# ADC.net
KiCad netlist of a schematic drawn in Altium Designer
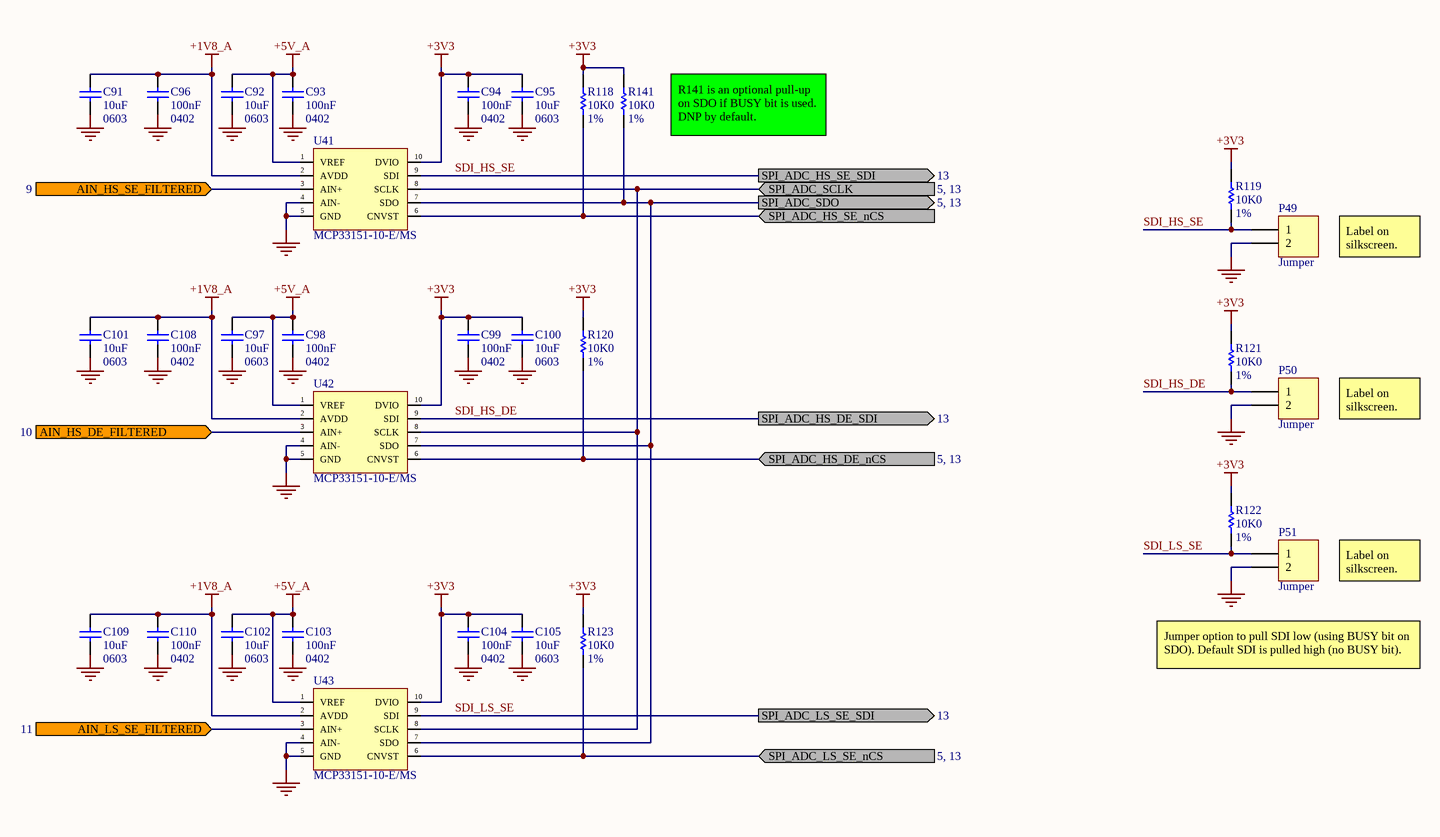
[diagram p0: ADC.SchDoc]

(export (version "E")
  (design (tool "Eeschema 10.0.6"))
  (components
    (comp (ref "C91")
      (value "10uF")
      (footprint "0603 CAP SAMSUNG CL10C")
      (description "Capacitor")
      (fields (field (name "ALTIUM_VALUE") "0603") (field (name "PUBLISHER") "Altium Limited"))
      (libsource (lib "Miscellaneous Devices") (part "Cap"))
    )
    (comp (ref "C92")
      (value "10uF")
      (footprint "0603 CAP SAMSUNG CL10C")
      (description "Capacitor")
      (fields (field (name "ALTIUM_VALUE") "0603") (field (name "PUBLISHER") "Altium Limited"))
      (libsource (lib "Miscellaneous Devices") (part "Cap"))
    )
    (comp (ref "C93")
      (value "100nF")
      (footprint "0402 CAP")
      (description "Capacitor")
      (fields (field (name "ALTIUM_VALUE") "0402") (field (name "PUBLISHER") "Altium Limited"))
      (libsource (lib "Miscellaneous Devices") (part "Cap"))
    )
    (comp (ref "C94")
      (value "100nF")
      (footprint "0402 CAP")
      (description "Capacitor")
      (fields (field (name "ALTIUM_VALUE") "0402") (field (name "PUBLISHER") "Altium Limited"))
      (libsource (lib "Miscellaneous Devices") (part "Cap"))
    )
    (comp (ref "C95")
      (value "10uF")
      (footprint "0603 CAP SAMSUNG CL10C")
      (description "Capacitor")
      (fields (field (name "ALTIUM_VALUE") "0603") (field (name "PUBLISHER") "Altium Limited"))
      (libsource (lib "Miscellaneous Devices") (part "Cap"))
    )
    (comp (ref "C96")
      (value "100nF")
      (footprint "0402 CAP")
      (description "Capacitor")
      (fields (field (name "ALTIUM_VALUE") "0402") (field (name "PUBLISHER") "Altium Limited"))
      (libsource (lib "Miscellaneous Devices") (part "Cap"))
    )
    (comp (ref "C97")
      (value "10uF")
      (footprint "0603 CAP SAMSUNG CL10C")
      (description "Capacitor")
      (fields (field (name "ALTIUM_VALUE") "0603") (field (name "PUBLISHER") "Altium Limited"))
      (libsource (lib "Miscellaneous Devices") (part "Cap"))
    )
    (comp (ref "C98")
      (value "100nF")
      (footprint "0402 CAP")
      (description "Capacitor")
      (fields (field (name "ALTIUM_VALUE") "0402") (field (name "PUBLISHER") "Altium Limited"))
      (libsource (lib "Miscellaneous Devices") (part "Cap"))
    )
    (comp (ref "C99")
      (value "100nF")
      (footprint "0402 CAP")
      (description "Capacitor")
      (fields (field (name "ALTIUM_VALUE") "0402") (field (name "PUBLISHER") "Altium Limited"))
      (libsource (lib "Miscellaneous Devices") (part "Cap"))
    )
    (comp (ref "C100")
      (value "10uF")
      (footprint "0603 CAP SAMSUNG CL10C")
      (description "Capacitor")
      (fields (field (name "ALTIUM_VALUE") "0603") (field (name "PUBLISHER") "Altium Limited"))
      (libsource (lib "Miscellaneous Devices") (part "Cap"))
    )
    (comp (ref "C101")
      (value "10uF")
      (footprint "0603 CAP SAMSUNG CL10C")
      (description "Capacitor")
      (fields (field (name "ALTIUM_VALUE") "0603") (field (name "PUBLISHER") "Altium Limited"))
      (libsource (lib "Miscellaneous Devices") (part "Cap"))
    )
    (comp (ref "C102")
      (value "10uF")
      (footprint "0603 CAP SAMSUNG CL10C")
      (description "Capacitor")
      (fields (field (name "ALTIUM_VALUE") "0603") (field (name "PUBLISHER") "Altium Limited"))
      (libsource (lib "Miscellaneous Devices") (part "Cap"))
    )
    (comp (ref "C103")
      (value "100nF")
      (footprint "0402 CAP")
      (description "Capacitor")
      (fields (field (name "ALTIUM_VALUE") "0402") (field (name "PUBLISHER") "Altium Limited"))
      (libsource (lib "Miscellaneous Devices") (part "Cap"))
    )
    (comp (ref "C104")
      (value "100nF")
      (footprint "0402 CAP")
      (description "Capacitor")
      (fields (field (name "ALTIUM_VALUE") "0402") (field (name "PUBLISHER") "Altium Limited"))
      (libsource (lib "Miscellaneous Devices") (part "Cap"))
    )
    (comp (ref "C105")
      (value "10uF")
      (footprint "0603 CAP SAMSUNG CL10C")
      (description "Capacitor")
      (fields (field (name "ALTIUM_VALUE") "0603") (field (name "PUBLISHER") "Altium Limited"))
      (libsource (lib "Miscellaneous Devices") (part "Cap"))
    )
    (comp (ref "C108")
      (value "100nF")
      (footprint "0402 CAP")
      (description "Capacitor")
      (fields (field (name "ALTIUM_VALUE") "0402") (field (name "PUBLISHER") "Altium Limited"))
      (libsource (lib "Miscellaneous Devices") (part "Cap"))
    )
    (comp (ref "C109")
      (value "10uF")
      (footprint "0603 CAP SAMSUNG CL10C")
      (description "Capacitor")
      (fields (field (name "ALTIUM_VALUE") "0603") (field (name "PUBLISHER") "Altium Limited"))
      (libsource (lib "Miscellaneous Devices") (part "Cap"))
    )
    (comp (ref "C110")
      (value "100nF")
      (footprint "0402 CAP")
      (description "Capacitor")
      (fields (field (name "ALTIUM_VALUE") "0402") (field (name "PUBLISHER") "Altium Limited"))
      (libsource (lib "Miscellaneous Devices") (part "Cap"))
    )
    (comp (ref "P49")
      (value "Jumper")
      (footprint "HDR1X2")
      (description "Header, 2-Pin")
      (fields (field (name "PUBLISHER") "Altium Limited"))
      (libsource (lib "Miscellaneous Connectors") (part "Header 2"))
    )
    (comp (ref "P50")
      (value "Jumper")
      (footprint "HDR1X2")
      (description "Header, 2-Pin")
      (fields (field (name "PUBLISHER") "Altium Limited"))
      (libsource (lib "Miscellaneous Connectors") (part "Header 2"))
    )
    (comp (ref "P51")
      (value "Jumper")
      (footprint "HDR1X2")
      (description "Header, 2-Pin")
      (fields (field (name "PUBLISHER") "Altium Limited"))
      (libsource (lib "Miscellaneous Connectors") (part "Header 2"))
    )
    (comp (ref "R118")
      (value "10K0")
      (footprint "0402 RES")
      (description "Resistor")
      (fields (field (name "ALTIUM_VALUE") "1%") (field (name "PUBLISHER") "Altium Limited"))
      (libsource (lib "Miscellaneous Devices") (part "Res1"))
    )
    (comp (ref "R119")
      (value "10K0")
      (footprint "0402 RES")
      (description "Resistor")
      (fields (field (name "ALTIUM_VALUE") "1%") (field (name "PUBLISHER") "Altium Limited"))
      (libsource (lib "Miscellaneous Devices") (part "Res1"))
    )
    (comp (ref "R120")
      (value "10K0")
      (footprint "0402 RES")
      (description "Resistor")
      (fields (field (name "ALTIUM_VALUE") "1%") (field (name "PUBLISHER") "Altium Limited"))
      (libsource (lib "Miscellaneous Devices") (part "Res1"))
    )
    (comp (ref "R121")
      (value "10K0")
      (footprint "0402 RES")
      (description "Resistor")
      (fields (field (name "ALTIUM_VALUE") "1%") (field (name "PUBLISHER") "Altium Limited"))
      (libsource (lib "Miscellaneous Devices") (part "Res1"))
    )
    (comp (ref "R122")
      (value "10K0")
      (footprint "0402 RES")
      (description "Resistor")
      (fields (field (name "ALTIUM_VALUE") "1%") (field (name "PUBLISHER") "Altium Limited"))
      (libsource (lib "Miscellaneous Devices") (part "Res1"))
    )
    (comp (ref "R123")
      (value "10K0")
      (footprint "0402 RES")
      (description "Resistor")
      (fields (field (name "ALTIUM_VALUE") "1%") (field (name "PUBLISHER") "Altium Limited"))
      (libsource (lib "Miscellaneous Devices") (part "Res1"))
    )
    (comp (ref "R141")
      (value "10K0")
      (footprint "0402 RES")
      (description "Resistor")
      (fields (field (name "ALTIUM_VALUE") "1%") (field (name "PUBLISHER") "Altium Limited"))
      (libsource (lib "Miscellaneous Devices") (part "Res1"))
    )
    (comp (ref "U41")
      (value "MCP33151-10-E/MS")
      (footprint "MSOP-10")
      (description "ADC 14-bit SAR 1Msps 10-MSOP")
      (fields (field (name "MANUFACTURER") "Microchip"))
      (libsource (lib "MRT SCH Library") (part "ADC MCP33151"))
    )
    (comp (ref "U42")
      (value "MCP33151-10-E/MS")
      (footprint "MSOP-10")
      (description "ADC 14-bit SAR 1Msps 10-MSOP")
      (fields (field (name "MANUFACTURER") "Microchip"))
      (libsource (lib "MRT SCH Library") (part "ADC MCP33151"))
    )
    (comp (ref "U43")
      (value "MCP33151-10-E/MS")
      (footprint "MSOP-10")
      (description "ADC 14-bit SAR 1Msps 10-MSOP")
      (fields (field (name "MANUFACTURER") "Microchip"))
      (libsource (lib "MRT SCH Library") (part "ADC MCP33151"))
    )
  )
  (nets
    (net (code "1") (name "+1V8_A") (class "Default")
      (node (ref "C101") (pin "2") (pinfunction "2_2") (pintype "passive"))
      (node (ref "C108") (pin "2") (pinfunction "2_2") (pintype "passive"))
      (node (ref "C109") (pin "2") (pinfunction "2_2") (pintype "passive"))
      (node (ref "C110") (pin "2") (pinfunction "2_2") (pintype "passive"))
      (node (ref "C91") (pin "2") (pinfunction "2_2") (pintype "passive"))
      (node (ref "C96") (pin "2") (pinfunction "2_2") (pintype "passive"))
      (node (ref "U41") (pin "2") (pinfunction "AVDD_2") (pintype "passive"))
      (node (ref "U42") (pin "2") (pinfunction "AVDD_2") (pintype "passive"))
      (node (ref "U43") (pin "2") (pinfunction "AVDD_2") (pintype "passive"))
    )
    (net (code "2") (name "+3V3") (class "Default")
      (node (ref "C100") (pin "2") (pinfunction "2_2") (pintype "passive"))
      (node (ref "C104") (pin "2") (pinfunction "2_2") (pintype "passive"))
      (node (ref "C105") (pin "2") (pinfunction "2_2") (pintype "passive"))
      (node (ref "C94") (pin "2") (pinfunction "2_2") (pintype "passive"))
      (node (ref "C95") (pin "2") (pinfunction "2_2") (pintype "passive"))
      (node (ref "C99") (pin "2") (pinfunction "2_2") (pintype "passive"))
      (node (ref "R118") (pin "2") (pinfunction "2_2") (pintype "passive"))
      (node (ref "R119") (pin "2") (pinfunction "2_2") (pintype "passive"))
      (node (ref "R120") (pin "2") (pinfunction "2_2") (pintype "passive"))
      (node (ref "R121") (pin "2") (pinfunction "2_2") (pintype "passive"))
      (node (ref "R122") (pin "2") (pinfunction "2_2") (pintype "passive"))
      (node (ref "R123") (pin "2") (pinfunction "2_2") (pintype "passive"))
      (node (ref "R141") (pin "2") (pinfunction "2_2") (pintype "passive"))
      (node (ref "U41") (pin "10") (pinfunction "DVIO_10") (pintype "passive"))
      (node (ref "U42") (pin "10") (pinfunction "DVIO_10") (pintype "passive"))
      (node (ref "U43") (pin "10") (pinfunction "DVIO_10") (pintype "passive"))
    )
    (net (code "3") (name "+5V_A") (class "Default")
      (node (ref "C102") (pin "2") (pinfunction "2_2") (pintype "passive"))
      (node (ref "C103") (pin "2") (pinfunction "2_2") (pintype "passive"))
      (node (ref "C92") (pin "2") (pinfunction "2_2") (pintype "passive"))
      (node (ref "C93") (pin "2") (pinfunction "2_2") (pintype "passive"))
      (node (ref "C97") (pin "2") (pinfunction "2_2") (pintype "passive"))
      (node (ref "C98") (pin "2") (pinfunction "2_2") (pintype "passive"))
      (node (ref "U41") (pin "1") (pinfunction "VREF_1") (pintype "passive"))
      (node (ref "U42") (pin "1") (pinfunction "VREF_1") (pintype "passive"))
      (node (ref "U43") (pin "1") (pinfunction "VREF_1") (pintype "passive"))
    )
    (net (code "4") (name "/AIN_HS_DE_FILTERED") (class "Default")
      (node (ref "U42") (pin "3") (pinfunction "AIN+_3") (pintype "passive"))
    )
    (net (code "5") (name "/AIN_HS_SE_FILTERED") (class "Default")
      (node (ref "U41") (pin "3") (pinfunction "AIN+_3") (pintype "passive"))
    )
    (net (code "6") (name "/AIN_LS_SE_FILTERED") (class "Default")
      (node (ref "U43") (pin "3") (pinfunction "AIN+_3") (pintype "passive"))
    )
    (net (code "7") (name "/SDI_HS_DE") (class "Default")
      (node (ref "P50") (pin "1") (pinfunction "1_1") (pintype "passive"))
      (node (ref "R121") (pin "1") (pinfunction "1_1") (pintype "passive"))
      (node (ref "U42") (pin "9") (pinfunction "SDI_9") (pintype "passive"))
    )
    (net (code "8") (name "/SDI_HS_SE") (class "Default")
      (node (ref "P49") (pin "1") (pinfunction "1_1") (pintype "passive"))
      (node (ref "R119") (pin "1") (pinfunction "1_1") (pintype "passive"))
      (node (ref "U41") (pin "9") (pinfunction "SDI_9") (pintype "passive"))
    )
    (net (code "9") (name "/SDI_LS_SE") (class "Default")
      (node (ref "P51") (pin "1") (pinfunction "1_1") (pintype "passive"))
      (node (ref "R122") (pin "1") (pinfunction "1_1") (pintype "passive"))
      (node (ref "U43") (pin "9") (pinfunction "SDI_9") (pintype "passive"))
    )
    (net (code "10") (name "/SPI_ADC_HS_DE_nCS") (class "Default")
      (node (ref "R120") (pin "1") (pinfunction "1_1") (pintype "passive"))
      (node (ref "U42") (pin "6") (pinfunction "CNVST_6") (pintype "passive"))
    )
    (net (code "11") (name "/SPI_ADC_HS_SE_nCS") (class "Default")
      (node (ref "R118") (pin "1") (pinfunction "1_1") (pintype "passive"))
      (node (ref "U41") (pin "6") (pinfunction "CNVST_6") (pintype "passive"))
    )
    (net (code "12") (name "/SPI_ADC_LS_SE_nCS") (class "Default")
      (node (ref "R123") (pin "1") (pinfunction "1_1") (pintype "passive"))
      (node (ref "U43") (pin "6") (pinfunction "CNVST_6") (pintype "passive"))
    )
    (net (code "13") (name "/SPI_ADC_SCLK") (class "Default")
      (node (ref "U41") (pin "8") (pinfunction "SCLK_8") (pintype "passive"))
      (node (ref "U42") (pin "8") (pinfunction "SCLK_8") (pintype "passive"))
      (node (ref "U43") (pin "8") (pinfunction "SCLK_8") (pintype "passive"))
    )
    (net (code "14") (name "/SPI_ADC_SDO") (class "Default")
      (node (ref "R141") (pin "1") (pinfunction "1_1") (pintype "passive"))
      (node (ref "U41") (pin "7") (pinfunction "SDO_7") (pintype "passive"))
      (node (ref "U42") (pin "7") (pinfunction "SDO_7") (pintype "passive"))
      (node (ref "U43") (pin "7") (pinfunction "SDO_7") (pintype "passive"))
    )
    (net (code "15") (name "GND") (class "Default")
      (node (ref "C100") (pin "1") (pinfunction "1_1") (pintype "passive"))
      (node (ref "C101") (pin "1") (pinfunction "1_1") (pintype "passive"))
      (node (ref "C102") (pin "1") (pinfunction "1_1") (pintype "passive"))
      (node (ref "C103") (pin "1") (pinfunction "1_1") (pintype "passive"))
      (node (ref "C104") (pin "1") (pinfunction "1_1") (pintype "passive"))
      (node (ref "C105") (pin "1") (pinfunction "1_1") (pintype "passive"))
      (node (ref "C108") (pin "1") (pinfunction "1_1") (pintype "passive"))
      (node (ref "C109") (pin "1") (pinfunction "1_1") (pintype "passive"))
      (node (ref "C110") (pin "1") (pinfunction "1_1") (pintype "passive"))
      (node (ref "C91") (pin "1") (pinfunction "1_1") (pintype "passive"))
      (node (ref "C92") (pin "1") (pinfunction "1_1") (pintype "passive"))
      (node (ref "C93") (pin "1") (pinfunction "1_1") (pintype "passive"))
      (node (ref "C94") (pin "1") (pinfunction "1_1") (pintype "passive"))
      (node (ref "C95") (pin "1") (pinfunction "1_1") (pintype "passive"))
      (node (ref "C96") (pin "1") (pinfunction "1_1") (pintype "passive"))
      (node (ref "C97") (pin "1") (pinfunction "1_1") (pintype "passive"))
      (node (ref "C98") (pin "1") (pinfunction "1_1") (pintype "passive"))
      (node (ref "C99") (pin "1") (pinfunction "1_1") (pintype "passive"))
      (node (ref "P49") (pin "2") (pinfunction "2_2") (pintype "passive"))
      (node (ref "P50") (pin "2") (pinfunction "2_2") (pintype "passive"))
      (node (ref "P51") (pin "2") (pinfunction "2_2") (pintype "passive"))
      (node (ref "U41") (pin "4") (pinfunction "AIN-_4") (pintype "passive"))
      (node (ref "U41") (pin "5") (pinfunction "GND_5") (pintype "passive"))
      (node (ref "U42") (pin "4") (pinfunction "AIN-_4") (pintype "passive"))
      (node (ref "U42") (pin "5") (pinfunction "GND_5") (pintype "passive"))
      (node (ref "U43") (pin "4") (pinfunction "AIN-_4") (pintype "passive"))
      (node (ref "U43") (pin "5") (pinfunction "GND_5") (pintype "passive"))
    )
  )
)
